# BLE.net
KiCad netlist of a schematic drawn in EAGLE
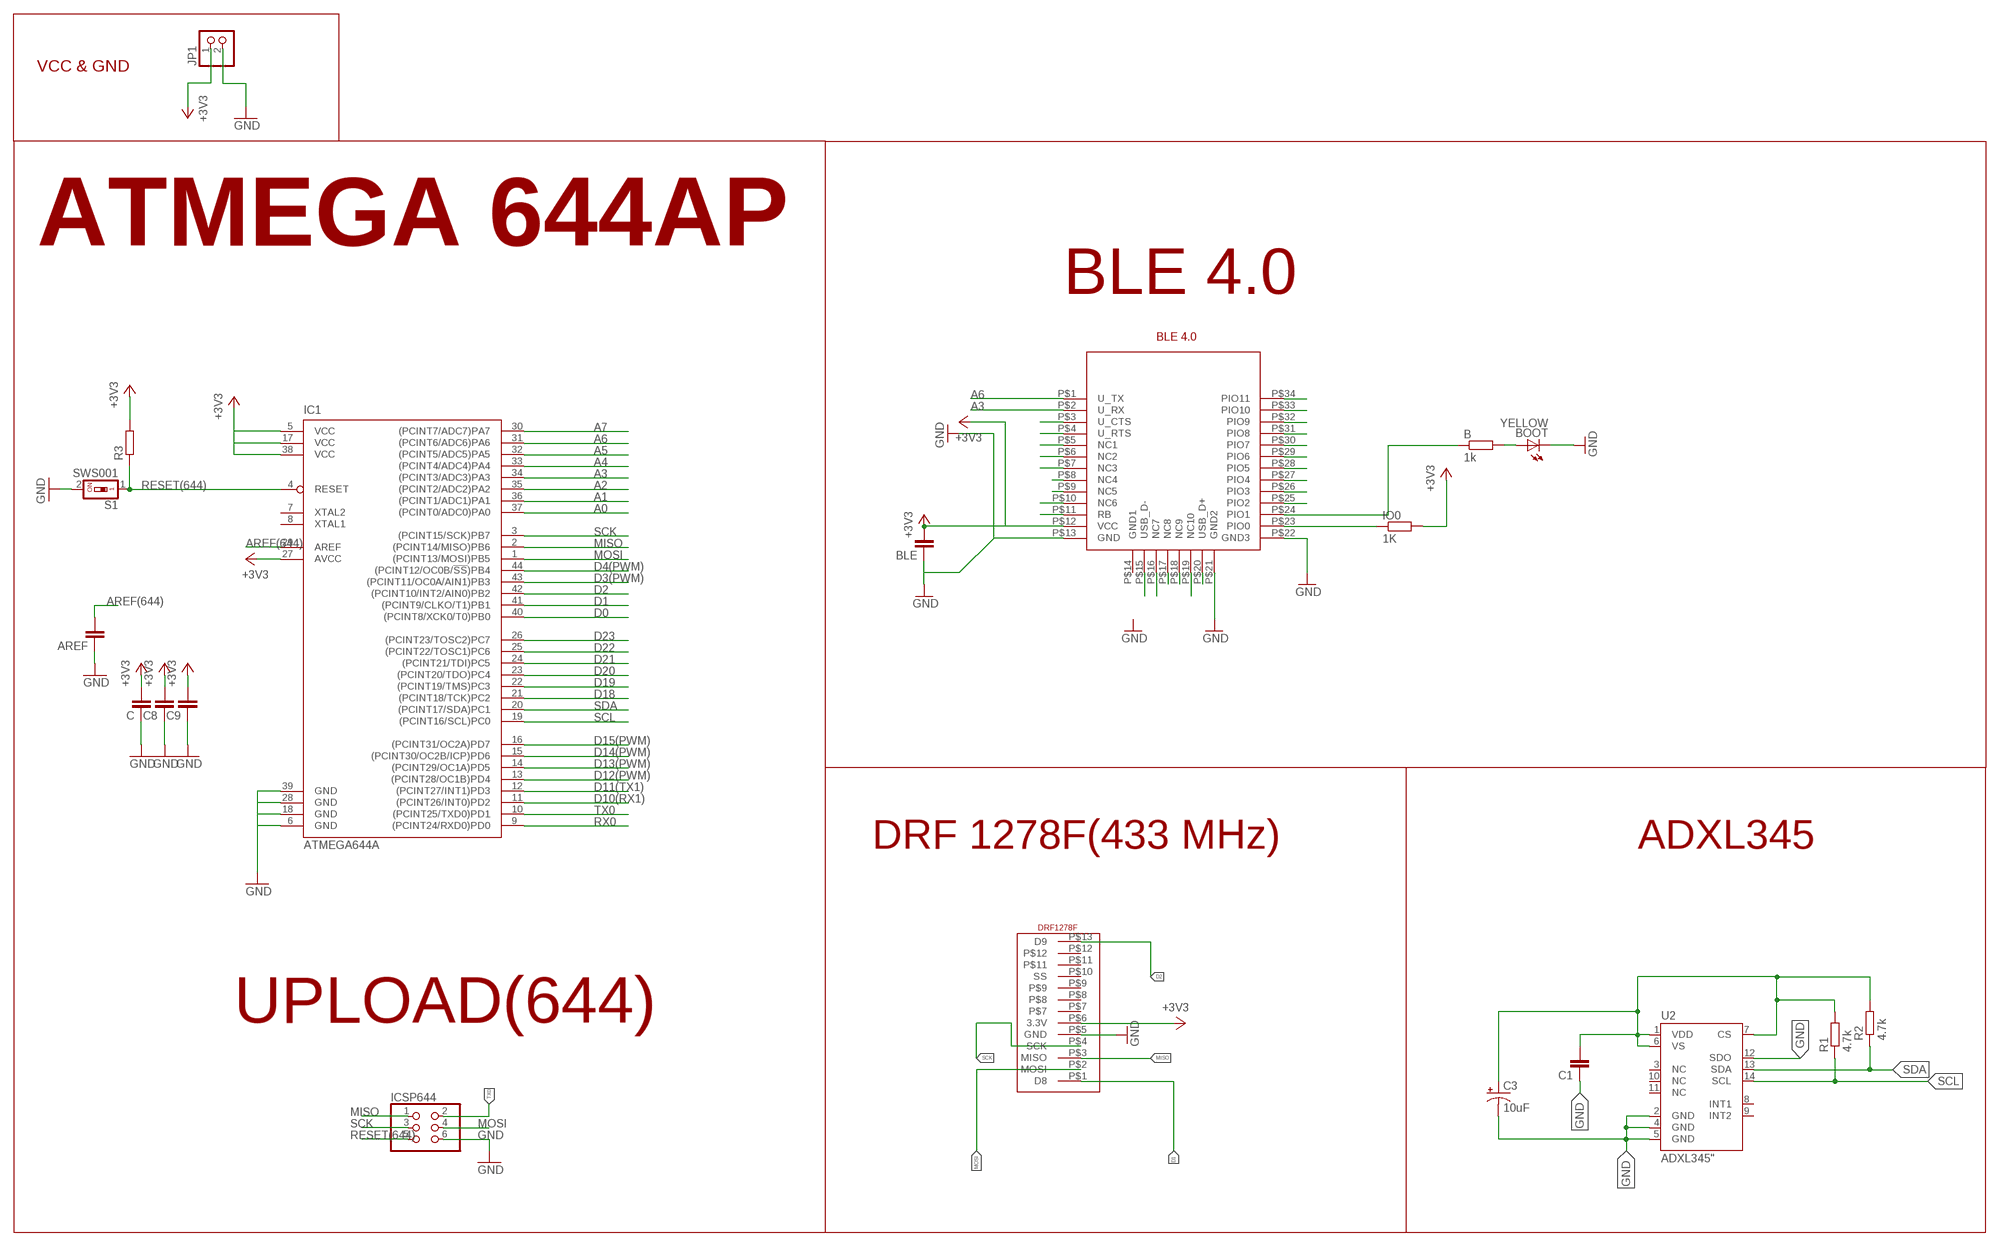
[diagram p0: schematic, sheet 1]

(export (version "E")
  (design (tool "Eeschema 10.0.6"))
  (components
    (comp (ref "AREF")
      (value "100nF")
      (footprint "eagle-import:C0805")
      (libsource (lib "eagle-import") (part "C-EUC0805"))
    )
    (comp (ref "B")
      (value "1k")
      (footprint "eagle-import:R0805")
      (libsource (lib "eagle-import") (part "R-EU_R0805"))
    )
    (comp (ref "BLE")
      (value "100nF")
      (footprint "eagle-import:C0805")
      (libsource (lib "eagle-import") (part "C-EUC0805"))
    )
    (comp (ref "BOOT")
      (value "YELLOW")
      (footprint "eagle-import:CHIP-LED0805")
      (libsource (lib "eagle-import") (part "LEDCHIP-LED0805"))
    )
    (comp (ref "C")
      (value "22 uF")
      (footprint "eagle-import:C0805")
      (libsource (lib "eagle-import") (part "C-EUC0805"))
    )
    (comp (ref "C1")
      (value "0.1uF")
      (footprint "eagle-import:C0805")
      (libsource (lib "eagle-import") (part "C-EUC0805"))
    )
    (comp (ref "C3")
      (value "10uF")
      (footprint "eagle-import:EIA3216")
      (libsource (lib "eagle-import") (part "CAP_POL1206"))
    )
    (comp (ref "C8")
      (value "100nF")
      (footprint "eagle-import:C0805")
      (libsource (lib "eagle-import") (part "C-EUC0805"))
    )
    (comp (ref "C9")
      (value "100nF")
      (footprint "eagle-import:C0805")
      (libsource (lib "eagle-import") (part "C-EUC0805"))
    )
    (comp (ref "IC1")
      (value "ATMEGA644A")
      (footprint "eagle-import:TQFP44")
      (fields (field (name "MPN") "ATMEGA644PV-10AU"))
      (libsource (lib "eagle-import") (part "ATMEGA644A"))
    )
    (comp (ref "ICSP644")
      (value "PINHD-2X3")
      (footprint "eagle-import:2X03")
      (libsource (lib "eagle-import") (part "PINHD-2X3"))
    )
    (comp (ref "IO0")
      (value "1K")
      (footprint "eagle-import:R0805")
      (libsource (lib "eagle-import") (part "R-EU_R0805"))
    )
    (comp (ref "JP1")
      (value "PINHD-1X2")
      (footprint "eagle-import:1X02")
      (libsource (lib "eagle-import") (part "PINHD-1X2"))
    )
    (comp (ref "R1")
      (value "4.7k")
      (footprint "eagle-import:R0805")
      (libsource (lib "eagle-import") (part "R-EU_R0805"))
    )
    (comp (ref "R2")
      (value "4.7k")
      (footprint "eagle-import:R0805")
      (libsource (lib "eagle-import") (part "R-EU_R0805"))
    )
    (comp (ref "R3")
      (value "R-EU_R0805")
      (footprint "eagle-import:R0805")
      (libsource (lib "eagle-import") (part "R-EU_R0805"))
    )
    (comp (ref "S1")
      (value "SWS001")
      (footprint "eagle-import:SMS-001")
      (libsource (lib "eagle-import") (part "SWS001"))
    )
    (comp (ref "U$1")
      (value "DRF1278F")
      (footprint "eagle-import:DIP13")
      (libsource (lib "eagle-import") (part "DRF1278F"))
    )
    (comp (ref "U$6")
      (value "BLUETOOTH_4.0(13)")
      (footprint "eagle-import:BLUTOOTH_4.0(13)")
      (libsource (lib "eagle-import") (part "BLUETOOTH_4.0(13)"))
    )
    (comp (ref "U2")
      (value "ADXL345\"")
      (footprint "eagle-import:ADXL3451_1")
      (libsource (lib "eagle-import") (part "ADXL345{dblquote}"))
    )
  )
  (nets
    (net (code "1") (name "+3V3") (class "Default")
      (node (ref "BLE") (pin "2") (pinfunction "2_2") (pintype "passive"))
      (node (ref "C") (pin "2") (pinfunction "2_2") (pintype "passive"))
      (node (ref "C8") (pin "2") (pinfunction "2_2") (pintype "passive"))
      (node (ref "C9") (pin "2") (pinfunction "2_2") (pintype "passive"))
      (node (ref "IC1") (pin "17") (pinfunction "VCC_17") (pintype "power_in"))
      (node (ref "IC1") (pin "27") (pinfunction "AVCC_27") (pintype "power_in"))
      (node (ref "IC1") (pin "38") (pinfunction "VCC_38") (pintype "power_in"))
      (node (ref "IC1") (pin "5") (pinfunction "VCC_5") (pintype "power_in"))
      (node (ref "IO0") (pin "2") (pinfunction "2_2") (pintype "passive"))
      (node (ref "JP1") (pin "1") (pinfunction "1_1") (pintype "passive"))
      (node (ref "R3") (pin "2") (pinfunction "2_2") (pintype "passive"))
      (node (ref "U$1") (pin "P$6") (pinfunction "3.3V_P$6") (pintype "bidirectional"))
      (node (ref "U$6") (pin "P$12") (pinfunction "VCC_P$12") (pintype "bidirectional"))
    )
    (net (code "2") (name "/A0") (class "Default")
      (node (ref "IC1") (pin "37") (pinfunction "(PCINT0/ADC0)PA0_37") (pintype "bidirectional"))
    )
    (net (code "3") (name "/A1") (class "Default")
      (node (ref "IC1") (pin "36") (pinfunction "(PCINT1/ADC1)PA1_36") (pintype "bidirectional"))
    )
    (net (code "4") (name "/A2") (class "Default")
      (node (ref "IC1") (pin "35") (pinfunction "(PCINT2/ADC2)PA2_35") (pintype "bidirectional"))
    )
    (net (code "5") (name "/A3") (class "Default")
      (node (ref "IC1") (pin "34") (pinfunction "(PCINT3/ADC3)PA3_34") (pintype "bidirectional"))
      (node (ref "U$6") (pin "P$2") (pinfunction "U_RX_P$2") (pintype "bidirectional"))
    )
    (net (code "6") (name "/A4") (class "Default")
      (node (ref "IC1") (pin "33") (pinfunction "(PCINT4/ADC4)PA4_33") (pintype "bidirectional"))
    )
    (net (code "7") (name "/A5") (class "Default")
      (node (ref "IC1") (pin "32") (pinfunction "(PCINT5/ADC5)PA5_32") (pintype "bidirectional"))
    )
    (net (code "8") (name "/A6") (class "Default")
      (node (ref "IC1") (pin "31") (pinfunction "(PCINT6/ADC6)PA6_31") (pintype "bidirectional"))
      (node (ref "U$6") (pin "P$1") (pinfunction "U_TX_P$1") (pintype "bidirectional"))
    )
    (net (code "9") (name "/A7") (class "Default")
      (node (ref "IC1") (pin "30") (pinfunction "(PCINT7/ADC7)PA7_30") (pintype "bidirectional"))
    )
    (net (code "10") (name "/AREF(644)") (class "Default")
      (node (ref "AREF") (pin "2") (pinfunction "2_2") (pintype "passive"))
      (node (ref "IC1") (pin "29") (pinfunction "AREF_29") (pintype "passive"))
    )
    (net (code "11") (name "/D0") (class "Default")
      (node (ref "IC1") (pin "40") (pinfunction "(PCINT8/XCK0/T0)PB0_40") (pintype "bidirectional"))
    )
    (net (code "12") (name "/D3(PWM)") (class "Default")
      (node (ref "IC1") (pin "43") (pinfunction "(PCINT11/OC0A/AIN1)PB3_43") (pintype "bidirectional"))
    )
    (net (code "13") (name "/D4(PWM)") (class "Default")
      (node (ref "IC1") (pin "44") (pinfunction "(PCINT12/OC0B/~{SS})PB4_44") (pintype "bidirectional"))
    )
    (net (code "14") (name "/D10(RX1)") (class "Default")
      (node (ref "IC1") (pin "11") (pinfunction "(PCINT26/INT0)PD2_11") (pintype "bidirectional"))
    )
    (net (code "15") (name "/D11(TX1)") (class "Default")
      (node (ref "IC1") (pin "12") (pinfunction "(PCINT27/INT1)PD3_12") (pintype "bidirectional"))
    )
    (net (code "16") (name "/D12(PWM)") (class "Default")
      (node (ref "IC1") (pin "13") (pinfunction "(PCINT28/OC1B)PD4_13") (pintype "bidirectional"))
    )
    (net (code "17") (name "/D13(PWM)") (class "Default")
      (node (ref "IC1") (pin "14") (pinfunction "(PCINT29/OC1A)PD5_14") (pintype "bidirectional"))
    )
    (net (code "18") (name "/D14(PWM)") (class "Default")
      (node (ref "IC1") (pin "15") (pinfunction "(PCINT30/OC2B/ICP)PD6_15") (pintype "bidirectional"))
    )
    (net (code "19") (name "/D15(PWM)") (class "Default")
      (node (ref "IC1") (pin "16") (pinfunction "(PCINT31/OC2A)PD7_16") (pintype "bidirectional"))
    )
    (net (code "20") (name "/D18") (class "Default")
      (node (ref "IC1") (pin "21") (pinfunction "(PCINT18/TCK)PC2_21") (pintype "output"))
    )
    (net (code "21") (name "/D19") (class "Default")
      (node (ref "IC1") (pin "22") (pinfunction "(PCINT19/TMS)PC3_22") (pintype "output"))
    )
    (net (code "22") (name "/D20") (class "Default")
      (node (ref "IC1") (pin "23") (pinfunction "(PCINT20/TDO)PC4_23") (pintype "output"))
    )
    (net (code "23") (name "/D21") (class "Default")
      (node (ref "IC1") (pin "24") (pinfunction "(PCINT21/TDI)PC5_24") (pintype "output"))
    )
    (net (code "24") (name "/D22") (class "Default")
      (node (ref "IC1") (pin "25") (pinfunction "(PCINT22/TOSC1)PC6_25") (pintype "output"))
    )
    (net (code "25") (name "/D23") (class "Default")
      (node (ref "IC1") (pin "26") (pinfunction "(PCINT23/TOSC2)PC7_26") (pintype "output"))
    )
    (net (code "26") (name "/RESET(644)") (class "Default")
      (node (ref "IC1") (pin "4") (pinfunction "RESET_4") (pintype "input"))
      (node (ref "ICSP644") (pin "5") (pinfunction "5_5") (pintype "passive"))
      (node (ref "R3") (pin "1") (pinfunction "1_1") (pintype "passive"))
      (node (ref "S1") (pin "1") (pinfunction "1_1") (pintype "passive"))
    )
    (net (code "27") (name "/RX0") (class "Default")
      (node (ref "IC1") (pin "9") (pinfunction "(PCINT24/RXD0)PD0_9") (pintype "bidirectional"))
    )
    (net (code "28") (name "D1") (class "Default")
      (node (ref "IC1") (pin "41") (pinfunction "(PCINT9/CLKO/T1)PB1_41") (pintype "bidirectional"))
      (node (ref "U$1") (pin "P$1") (pinfunction "D8_P$1") (pintype "bidirectional"))
    )
    (net (code "29") (name "D2") (class "Default")
      (node (ref "IC1") (pin "42") (pinfunction "(PCINT10/INT2/AIN0)PB2_42") (pintype "bidirectional"))
      (node (ref "U$1") (pin "P$13") (pinfunction "D9_P$13") (pintype "bidirectional"))
    )
    (net (code "30") (name "GND") (class "Default")
      (node (ref "AREF") (pin "1") (pinfunction "1_1") (pintype "passive"))
      (node (ref "BLE") (pin "1") (pinfunction "1_1") (pintype "passive"))
      (node (ref "BOOT") (pin "C") (pinfunction "C_C") (pintype "passive"))
      (node (ref "C") (pin "1") (pinfunction "1_1") (pintype "passive"))
      (node (ref "C1") (pin "1") (pinfunction "1_1") (pintype "passive"))
      (node (ref "C3") (pin "C") (pinfunction "-_C") (pintype "passive"))
      (node (ref "C8") (pin "1") (pinfunction "1_1") (pintype "passive"))
      (node (ref "C9") (pin "1") (pinfunction "1_1") (pintype "passive"))
      (node (ref "IC1") (pin "18") (pinfunction "GND_18") (pintype "power_in"))
      (node (ref "IC1") (pin "28") (pinfunction "GND_28") (pintype "power_in"))
      (node (ref "IC1") (pin "39") (pinfunction "GND_39") (pintype "power_in"))
      (node (ref "IC1") (pin "6") (pinfunction "GND_6") (pintype "power_in"))
      (node (ref "ICSP644") (pin "6") (pinfunction "6_6") (pintype "passive"))
      (node (ref "JP1") (pin "2") (pinfunction "2_2") (pintype "passive"))
      (node (ref "S1") (pin "2") (pinfunction "2_2") (pintype "passive"))
      (node (ref "U$1") (pin "P$5") (pinfunction "GND_P$5") (pintype "bidirectional"))
      (node (ref "U$6") (pin "P$13") (pinfunction "GND_P$13") (pintype "bidirectional"))
      (node (ref "U$6") (pin "P$21") (pinfunction "GND2_P$21") (pintype "bidirectional"))
      (node (ref "U$6") (pin "P$22") (pinfunction "GND3_P$22") (pintype "bidirectional"))
      (node (ref "U2") (pin "12") (pinfunction "SDO_12") (pintype "bidirectional"))
      (node (ref "U2") (pin "2") (pinfunction "GND_2") (pintype "bidirectional"))
      (node (ref "U2") (pin "4") (pinfunction "GND_4") (pintype "bidirectional"))
      (node (ref "U2") (pin "5") (pinfunction "GND_5") (pintype "bidirectional"))
    )
    (net (code "31") (name "MISO") (class "Default")
      (node (ref "IC1") (pin "2") (pinfunction "(PCINT14/MISO)PB6_2") (pintype "bidirectional"))
      (node (ref "ICSP644") (pin "1") (pinfunction "1_1") (pintype "passive"))
      (node (ref "U$1") (pin "P$3") (pinfunction "MISO_P$3") (pintype "bidirectional"))
    )
    (net (code "32") (name "MOSI") (class "Default")
      (node (ref "IC1") (pin "1") (pinfunction "(PCINT13/MOSI)PB5_1") (pintype "bidirectional"))
      (node (ref "ICSP644") (pin "4") (pinfunction "4_4") (pintype "passive"))
      (node (ref "U$1") (pin "P$2") (pinfunction "MOSI_P$2") (pintype "bidirectional"))
    )
    (net (code "33") (name "Net-(B-Pad2)") (class "Default")
      (node (ref "B") (pin "2") (pinfunction "2_2") (pintype "passive"))
      (node (ref "BOOT") (pin "A") (pinfunction "A_A") (pintype "passive"))
    )
    (net (code "34") (name "Net-(C3-+)") (class "Default")
      (node (ref "C1") (pin "2") (pinfunction "2_2") (pintype "passive"))
      (node (ref "C3") (pin "A") (pinfunction "+_A") (pintype "passive"))
      (node (ref "R1") (pin "2") (pinfunction "2_2") (pintype "passive"))
      (node (ref "R2") (pin "2") (pinfunction "2_2") (pintype "passive"))
      (node (ref "U2") (pin "1") (pinfunction "VDD_1") (pintype "bidirectional"))
      (node (ref "U2") (pin "6") (pinfunction "VS_6") (pintype "bidirectional"))
      (node (ref "U2") (pin "7") (pinfunction "CS_7") (pintype "bidirectional"))
    )
    (net (code "35") (name "Net-(U$6-PIO0)") (class "Default")
      (node (ref "IO0") (pin "1") (pinfunction "1_1") (pintype "passive"))
      (node (ref "U$6") (pin "P$23") (pinfunction "PIO0_P$23") (pintype "bidirectional"))
    )
    (net (code "36") (name "Net-(U$6-PIO1)") (class "Default")
      (node (ref "B") (pin "1") (pinfunction "1_1") (pintype "passive"))
      (node (ref "U$6") (pin "P$24") (pinfunction "PIO1_P$24") (pintype "bidirectional"))
    )
    (net (code "37") (name "SCK") (class "Default")
      (node (ref "IC1") (pin "3") (pinfunction "(PCINT15/SCK)PB7_3") (pintype "bidirectional"))
      (node (ref "ICSP644") (pin "3") (pinfunction "3_3") (pintype "passive"))
      (node (ref "U$1") (pin "P$4") (pinfunction "SCK_P$4") (pintype "bidirectional"))
    )
    (net (code "38") (name "SCL") (class "Default")
      (node (ref "IC1") (pin "19") (pinfunction "(PCINT16/SCL)PC0_19") (pintype "output"))
      (node (ref "R1") (pin "1") (pinfunction "1_1") (pintype "passive"))
      (node (ref "U2") (pin "14") (pinfunction "SCL_14") (pintype "bidirectional"))
    )
    (net (code "39") (name "SDA") (class "Default")
      (node (ref "IC1") (pin "20") (pinfunction "(PCINT17/SDA)PC1_20") (pintype "output"))
      (node (ref "R2") (pin "1") (pinfunction "1_1") (pintype "passive"))
      (node (ref "U2") (pin "13") (pinfunction "SDA_13") (pintype "bidirectional"))
    )
    (net (code "40") (name "TX0") (class "Default")
      (node (ref "IC1") (pin "10") (pinfunction "(PCINT25/TXD0)PD1_10") (pintype "bidirectional"))
      (node (ref "ICSP644") (pin "2") (pinfunction "2_2") (pintype "passive"))
    )
    (net (code "41") (name "unconnected-(IC1-XTAL1-Pad8)") (class "Default")
      (node (ref "IC1") (pin "8") (pinfunction "XTAL1_8") (pintype "bidirectional"))
    )
    (net (code "42") (name "unconnected-(IC1-XTAL2-Pad7)") (class "Default")
      (node (ref "IC1") (pin "7") (pinfunction "XTAL2_7") (pintype "bidirectional"))
    )
    (net (code "43") (name "unconnected-(U$1-PadP$7)") (class "Default")
      (node (ref "U$1") (pin "P$7") (pinfunction "P$7_P$7") (pintype "bidirectional"))
    )
    (net (code "44") (name "unconnected-(U$1-PadP$8)") (class "Default")
      (node (ref "U$1") (pin "P$8") (pinfunction "P$8_P$8") (pintype "bidirectional"))
    )
    (net (code "45") (name "unconnected-(U$1-PadP$9)") (class "Default")
      (node (ref "U$1") (pin "P$9") (pinfunction "P$9_P$9") (pintype "bidirectional"))
    )
    (net (code "46") (name "unconnected-(U$1-PadP$11)") (class "Default")
      (node (ref "U$1") (pin "P$11") (pinfunction "P$11_P$11") (pintype "bidirectional"))
    )
    (net (code "47") (name "unconnected-(U$1-PadP$12)") (class "Default")
      (node (ref "U$1") (pin "P$12") (pinfunction "P$12_P$12") (pintype "bidirectional"))
    )
    (net (code "48") (name "unconnected-(U$1-SS-PadP$10)") (class "Default")
      (node (ref "U$1") (pin "P$10") (pinfunction "SS_P$10") (pintype "bidirectional"))
    )
    (net (code "49") (name "unconnected-(U$6-GND1-PadP$14)") (class "Default")
      (node (ref "U$6") (pin "P$14") (pinfunction "GND1_P$14") (pintype "bidirectional"))
    )
    (net (code "50") (name "unconnected-(U$6-NC1-PadP$5)") (class "Default")
      (node (ref "U$6") (pin "P$5") (pinfunction "NC1_P$5") (pintype "bidirectional"))
    )
    (net (code "51") (name "unconnected-(U$6-NC2-PadP$6)") (class "Default")
      (node (ref "U$6") (pin "P$6") (pinfunction "NC2_P$6") (pintype "bidirectional"))
    )
    (net (code "52") (name "unconnected-(U$6-NC3-PadP$7)") (class "Default")
      (node (ref "U$6") (pin "P$7") (pinfunction "NC3_P$7") (pintype "bidirectional"))
    )
    (net (code "53") (name "unconnected-(U$6-NC4-PadP$8)") (class "Default")
      (node (ref "U$6") (pin "P$8") (pinfunction "NC4_P$8") (pintype "bidirectional"))
    )
    (net (code "54") (name "unconnected-(U$6-NC5-PadP$9)") (class "Default")
      (node (ref "U$6") (pin "P$9") (pinfunction "NC5_P$9") (pintype "bidirectional"))
    )
    (net (code "55") (name "unconnected-(U$6-NC6-PadP$10)") (class "Default")
      (node (ref "U$6") (pin "P$10") (pinfunction "NC6_P$10") (pintype "bidirectional"))
    )
    (net (code "56") (name "unconnected-(U$6-NC7-PadP$16)") (class "Default")
      (node (ref "U$6") (pin "P$16") (pinfunction "NC7_P$16") (pintype "bidirectional"))
    )
    (net (code "57") (name "unconnected-(U$6-NC8-PadP$17)") (class "Default")
      (node (ref "U$6") (pin "P$17") (pinfunction "NC8_P$17") (pintype "bidirectional"))
    )
    (net (code "58") (name "unconnected-(U$6-NC9-PadP$18)") (class "Default")
      (node (ref "U$6") (pin "P$18") (pinfunction "NC9_P$18") (pintype "bidirectional"))
    )
    (net (code "59") (name "unconnected-(U$6-NC10-PadP$19)") (class "Default")
      (node (ref "U$6") (pin "P$19") (pinfunction "NC10_P$19") (pintype "bidirectional"))
    )
    (net (code "60") (name "unconnected-(U$6-PIO2-PadP$25)") (class "Default")
      (node (ref "U$6") (pin "P$25") (pinfunction "PIO2_P$25") (pintype "bidirectional"))
    )
    (net (code "61") (name "unconnected-(U$6-PIO3-PadP$26)") (class "Default")
      (node (ref "U$6") (pin "P$26") (pinfunction "PIO3_P$26") (pintype "bidirectional"))
    )
    (net (code "62") (name "unconnected-(U$6-PIO4-PadP$27)") (class "Default")
      (node (ref "U$6") (pin "P$27") (pinfunction "PIO4_P$27") (pintype "bidirectional"))
    )
    (net (code "63") (name "unconnected-(U$6-PIO5-PadP$28)") (class "Default")
      (node (ref "U$6") (pin "P$28") (pinfunction "PIO5_P$28") (pintype "bidirectional"))
    )
    (net (code "64") (name "unconnected-(U$6-PIO6-PadP$29)") (class "Default")
      (node (ref "U$6") (pin "P$29") (pinfunction "PIO6_P$29") (pintype "bidirectional"))
    )
    (net (code "65") (name "unconnected-(U$6-PIO7-PadP$30)") (class "Default")
      (node (ref "U$6") (pin "P$30") (pinfunction "PIO7_P$30") (pintype "bidirectional"))
    )
    (net (code "66") (name "unconnected-(U$6-PIO8-PadP$31)") (class "Default")
      (node (ref "U$6") (pin "P$31") (pinfunction "PIO8_P$31") (pintype "bidirectional"))
    )
    (net (code "67") (name "unconnected-(U$6-PIO9-PadP$32)") (class "Default")
      (node (ref "U$6") (pin "P$32") (pinfunction "PIO9_P$32") (pintype "bidirectional"))
    )
    (net (code "68") (name "unconnected-(U$6-PIO10-PadP$33)") (class "Default")
      (node (ref "U$6") (pin "P$33") (pinfunction "PIO10_P$33") (pintype "bidirectional"))
    )
    (net (code "69") (name "unconnected-(U$6-PIO11-PadP$34)") (class "Default")
      (node (ref "U$6") (pin "P$34") (pinfunction "PIO11_P$34") (pintype "bidirectional"))
    )
    (net (code "70") (name "unconnected-(U$6-RB-PadP$11)") (class "Default")
      (node (ref "U$6") (pin "P$11") (pinfunction "RB_P$11") (pintype "bidirectional"))
    )
    (net (code "71") (name "unconnected-(U$6-USB_D+-PadP$20)") (class "Default")
      (node (ref "U$6") (pin "P$20") (pinfunction "USB_D+_P$20") (pintype "bidirectional"))
    )
    (net (code "72") (name "unconnected-(U$6-USB_D--PadP$15)") (class "Default")
      (node (ref "U$6") (pin "P$15") (pinfunction "USB_D-_P$15") (pintype "bidirectional"))
    )
    (net (code "73") (name "unconnected-(U$6-U_CTS-PadP$3)") (class "Default")
      (node (ref "U$6") (pin "P$3") (pinfunction "U_CTS_P$3") (pintype "bidirectional"))
    )
    (net (code "74") (name "unconnected-(U$6-U_RTS-PadP$4)") (class "Default")
      (node (ref "U$6") (pin "P$4") (pinfunction "U_RTS_P$4") (pintype "bidirectional"))
    )
    (net (code "75") (name "unconnected-(U2-INT1-Pad8)") (class "Default")
      (node (ref "U2") (pin "8") (pinfunction "INT1_8") (pintype "bidirectional"))
    )
    (net (code "76") (name "unconnected-(U2-INT2-Pad9)") (class "Default")
      (node (ref "U2") (pin "9") (pinfunction "INT2_9") (pintype "bidirectional"))
    )
    (net (code "77") (name "unconnected-(U2-NC-Pad3)") (class "Default")
      (node (ref "U2") (pin "3") (pinfunction "NC_3") (pintype "bidirectional"))
    )
    (net (code "78") (name "unconnected-(U2-NC-Pad10)") (class "Default")
      (node (ref "U2") (pin "10") (pinfunction "NC_10") (pintype "bidirectional"))
    )
    (net (code "79") (name "unconnected-(U2-NC-Pad11)") (class "Default")
      (node (ref "U2") (pin "11") (pinfunction "NC_11") (pintype "bidirectional"))
    )
  )
)
